# CTR_Precharge.net
KiCad netlist of a schematic drawn in Altium Designer
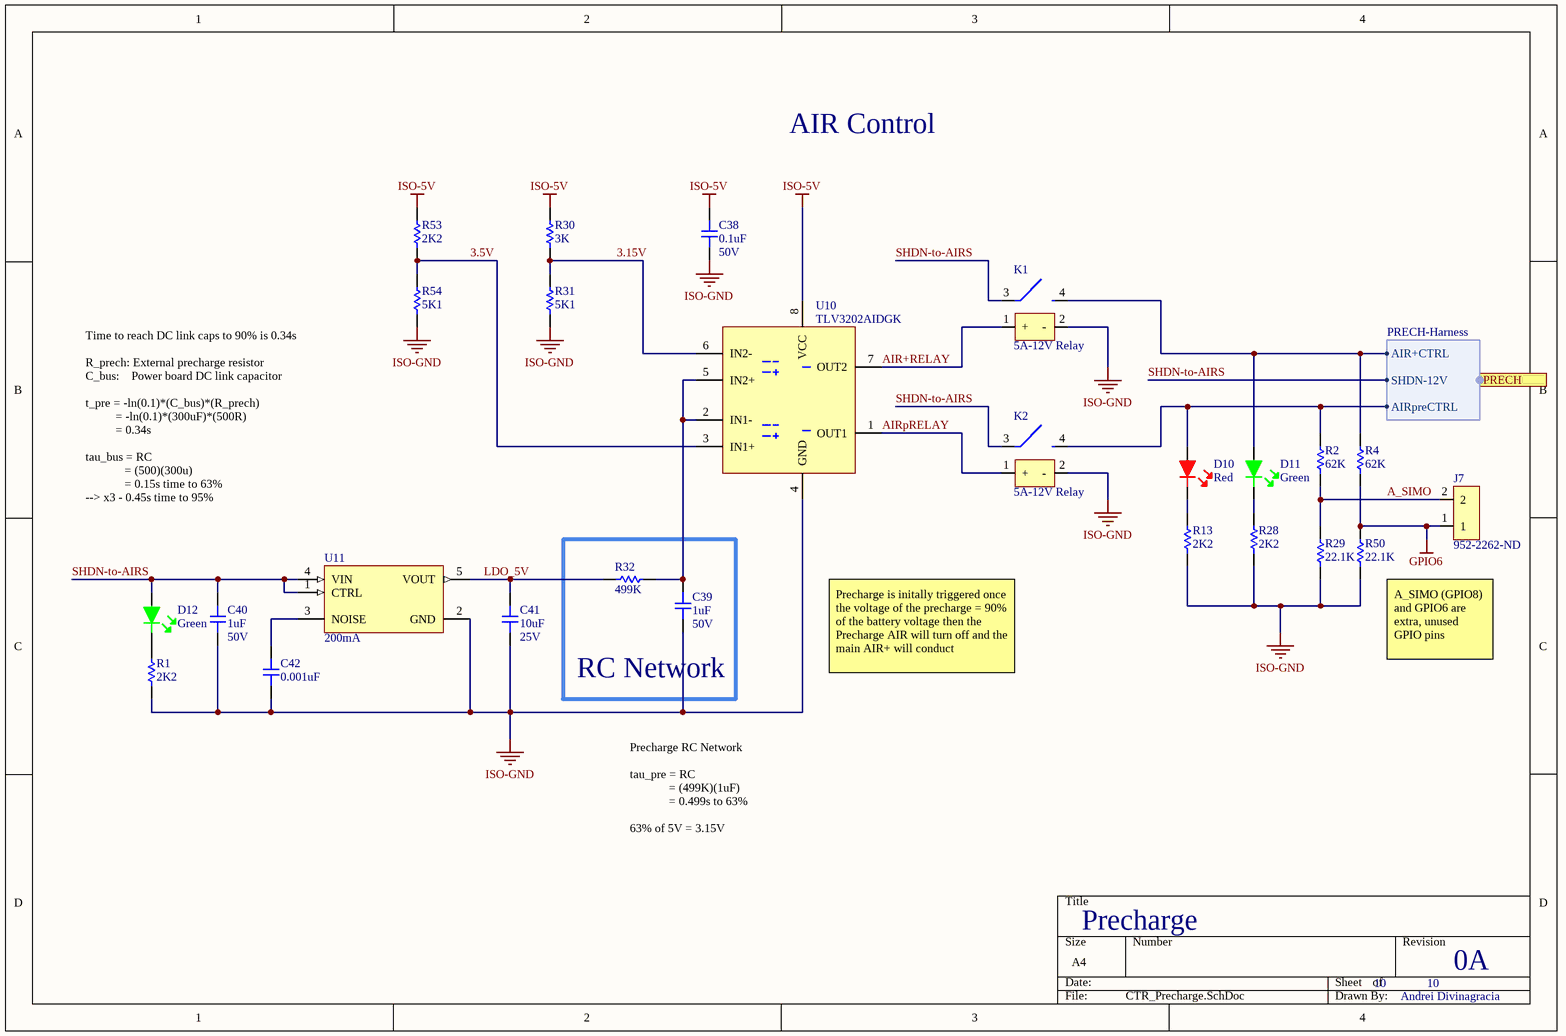
[diagram p0: CTR_Precharge.SchDoc]

(export (version "E")
  (design (tool "Eeschema 10.0.6"))
  (components
    (comp (ref "C38")
      (value "0.1uF")
      (footprint "CAP-0805")
      (description "CAP CER 0.1UF 50V Y5V 0805")
      (fields
        (field (name "MANUFACTURER") "KEMET")
        (field (name "MANUFACTURER PART NUMBER") "C0805C104Z5VACTU")
        (field (name "VOLTAGE RATING") "50V")
      )
      (libsource (lib "InverterSCHLib") (part "0805-0.1uF-50V"))
    )
    (comp (ref "C39")
      (value "1uF")
      (footprint "CAP-0805")
      (description "CAP CER 1UF 50V X5R 0805")
      (fields
        (field (name "MANUFACTURER") "KEMET")
        (field (name "MANUFACTURER PART NUMBER") "C0805C105K5PACTU")
        (field (name "VOLTAGE RATING") "50V")
      )
      (libsource (lib "InverterSCHLib") (part "0805-1uF-50V"))
    )
    (comp (ref "C40")
      (value "1uF")
      (footprint "CAP-0805")
      (description "CAP CER 1UF 50V X5R 0805")
      (fields
        (field (name "MANUFACTURER") "KEMET")
        (field (name "MANUFACTURER PART NUMBER") "C0805C105K5PACTU")
        (field (name "VOLTAGE RATING") "50V")
      )
      (libsource (lib "InverterSCHLib") (part "0805-1uF-50V"))
    )
    (comp (ref "C41")
      (value "10uF")
      (footprint "CAP-1206")
      (description "CAP CER 10UF 25V X7R 1206")
      (fields
        (field (name "MANUFACTURER") "Samsung")
        (field (name "MANUFACTURER PART NUMBER") "CL31B106KAHZW6E")
        (field (name "VOLTAGE RATING") "25V")
      )
      (libsource (lib "InverterSCHLib") (part "1206-10uF-25V"))
    )
    (comp (ref "C42")
      (value "0.001uF")
      (footprint "CAP-0603")
      (description "CAP CER 10000PF 50V X7R 0603")
      (fields
        (field (name "MANUFACTURER") "Kyocera AVX")
        (field (name "MANUFACTURER PART NUMBER") "06035C103KAT4A")
      )
      (libsource (lib "InverterSCHLib") (part "0603-10nF"))
    )
    (comp (ref "D10")
      (value "Red")
      (footprint "LED-0603")
      (description "LED RED CLEAR 0603 SMD")
      (fields
        (field (name "MANUFACTURER") "Wurth Electronics")
        (field (name "MANUFACTURER PART NUMBER") "150060RS75000")
      )
      (libsource (lib "InverterSCHLib") (part "LED-Red"))
    )
    (comp (ref "D11")
      (value "Green")
      (footprint "LED-0603")
      (description "LED GREEN CLEAR 0603 SMD")
      (fields
        (field (name "MANUFACTURER") "Wurth Electronics")
        (field (name "MANUFACTURER PART NUMBER") "150060VS75000")
      )
      (libsource (lib "InverterSCHLib") (part "LED-Green"))
    )
    (comp (ref "D12")
      (value "Green")
      (footprint "LED-0603")
      (description "LED GREEN CLEAR 0603 SMD")
      (fields
        (field (name "MANUFACTURER") "Wurth Electronics")
        (field (name "MANUFACTURER PART NUMBER") "150060VS75000")
      )
      (libsource (lib "InverterSCHLib") (part "LED-Green"))
    )
    (comp (ref "J7")
      (value "952-2262-ND")
      (footprint "2PIN_HEADER")
      (description "CONN HEADER VERT 2POS 2.54MM")
      (fields (field (name "MANUFACTURER") "Harwin") (field (name "MANUFACTURER PART NUMBER") "M20-9990246"))
      (libsource (lib "InverterSCHLib") (part "M20-9990246"))
    )
    (comp (ref "K1")
      (value "5A-12V Relay")
      (footprint "Relay")
      (description "General Purpose Relay SPST-NO (1 Form A) 12VDC Coil Through Hole")
      (fields
        (field (name "MANUFACTURER") "TE Connectivity")
        (field (name "MANUFACTURER PART NUMBER") "OJE-SH-112DM,000")
      )
      (libsource (lib "InverterSCHLib") (part "OJE-SH-112DM,000"))
    )
    (comp (ref "K2")
      (value "5A-12V Relay")
      (footprint "Relay")
      (description "General Purpose Relay SPST-NO (1 Form A) 12VDC Coil Through Hole")
      (fields
        (field (name "MANUFACTURER") "TE Connectivity")
        (field (name "MANUFACTURER PART NUMBER") "OJE-SH-112DM,000")
      )
      (libsource (lib "InverterSCHLib") (part "OJE-SH-112DM,000"))
    )
    (comp (ref "R1")
      (value "2K2")
      (footprint "RES-0603")
      (description "RES SMD 2.2K OHM 5% 1/10W 0603")
      (fields
        (field (name "MANUFACTURER") "Yageo")
        (field (name "MANUFACTURER PART NUMBER") "AC0603JR-072K2L")
      )
      (libsource (lib "InverterSCHLib") (part "0603-2K2"))
    )
    (comp (ref "R2")
      (value "62K")
      (footprint "RES-0603")
      (description "RES SMD 62K OHM 1% 1/4W 0603")
      (fields
        (field (name "MANUFACTURER") "Panasonic")
        (field (name "MANUFACTURER PART NUMBER") "ERJ-PA3F6202V")
      )
      (libsource (lib "InverterSCHLib") (part "0603-62K"))
    )
    (comp (ref "R4")
      (value "62K")
      (footprint "RES-0603")
      (description "RES SMD 62K OHM 1% 1/4W 0603")
      (fields
        (field (name "MANUFACTURER") "Panasonic")
        (field (name "MANUFACTURER PART NUMBER") "ERJ-PA3F6202V")
      )
      (libsource (lib "InverterSCHLib") (part "0603-62K"))
    )
    (comp (ref "R13")
      (value "2K2")
      (footprint "RES-0603")
      (description "RES SMD 2.2K OHM 5% 1/10W 0603")
      (fields
        (field (name "MANUFACTURER") "Yageo")
        (field (name "MANUFACTURER PART NUMBER") "AC0603JR-072K2L")
      )
      (libsource (lib "InverterSCHLib") (part "0603-2K2"))
    )
    (comp (ref "R28")
      (value "2K2")
      (footprint "RES-0603")
      (description "RES SMD 2.2K OHM 5% 1/10W 0603")
      (fields
        (field (name "MANUFACTURER") "Yageo")
        (field (name "MANUFACTURER PART NUMBER") "AC0603JR-072K2L")
      )
      (libsource (lib "InverterSCHLib") (part "0603-2K2"))
    )
    (comp (ref "R29")
      (value "22.1K")
      (footprint "RES-0603")
      (description "RES SMD 22.1K OHM 1% 1/10W 0603")
      (fields
        (field (name "MANUFACTURER") "Vishay")
        (field (name "MANUFACTURER PART NUMBER") "CRCW060322K1FKEA")
      )
      (libsource (lib "InverterSCHLib") (part "0603-22.1KR"))
    )
    (comp (ref "R30")
      (value "3K")
      (footprint "RES-0603")
      (description "RES SMD 3K OHM 5% 1/10W 0603")
      (fields
        (field (name "MANUFACTURER") "Yageo")
        (field (name "MANUFACTURER PART NUMBER") "RC0603JR-073KL")
      )
      (libsource (lib "InverterSCHLib") (part "0603-3KR"))
    )
    (comp (ref "R31")
      (value "5K1")
      (footprint "RES-0603")
      (description "RES SMD 5.1K OHM 1% 1/10W 0603")
      (fields
        (field (name "MANUFACTURER") "TE Connectivity")
        (field (name "MANUFACTURER PART NUMBER") "1623257-1")
      )
      (libsource (lib "InverterSCHLib") (part "0603-5.1KR"))
    )
    (comp (ref "R32")
      (value "499K")
      (footprint "RES-0603")
      (description "RES 499K OHM 1% 1/10W 0603")
      (fields
        (field (name "MANUFACTURER") "Vishay")
        (field (name "MANUFACTURER PART NUMBER") "CRCW0603499KFKEAC")
      )
      (libsource (lib "InverterSCHLib") (part "0603-499KR"))
    )
    (comp (ref "R50")
      (value "22.1K")
      (footprint "RES-0603")
      (description "RES SMD 22.1K OHM 1% 1/10W 0603")
      (fields
        (field (name "MANUFACTURER") "Vishay")
        (field (name "MANUFACTURER PART NUMBER") "CRCW060322K1FKEA")
      )
      (libsource (lib "InverterSCHLib") (part "0603-22.1KR"))
    )
    (comp (ref "R53")
      (value "2K2")
      (footprint "RES-0603")
      (description "RES SMD 2.2K OHM 5% 1/10W 0603")
      (fields
        (field (name "MANUFACTURER") "Yageo")
        (field (name "MANUFACTURER PART NUMBER") "AC0603JR-072K2L")
      )
      (libsource (lib "InverterSCHLib") (part "0603-2K2"))
    )
    (comp (ref "R54")
      (value "5K1")
      (footprint "RES-0603")
      (description "RES SMD 5.1K OHM 1% 1/10W 0603")
      (fields
        (field (name "MANUFACTURER") "TE Connectivity")
        (field (name "MANUFACTURER PART NUMBER") "1623257-1")
      )
      (libsource (lib "InverterSCHLib") (part "0603-5.1KR"))
    )
    (comp (ref "U10")
      (value "TLV3202AIDGK")
      (footprint "8VSSOP")
      (description "IC COMPAR PWR RRI DL PP 8VSSOP")
      (fields (field (name "MANUFACTURER") "Texas Instruments"))
      (libsource (lib "InverterSCHLib") (part "Compare-TLV3202AIDGK"))
    )
    (comp (ref "U11")
      (value "200mA")
      (footprint "SOT-753-ldo")
      (description "IC REG LINEAR 5V 200MA SMV")
      (fields
        (field (name "MANUFACTURER") "Toshiba")
        (field (name "MANUFACTURER PART NUMBER") "TAR5S50TE85LF")
      )
      (libsource (lib "InverterSCHLib") (part "TAR5S50TE85LF"))
    )
  )
  (nets
    (net (code "2") (name "/3.5V") (class "Default")
      (node (ref "R53") (pin "1") (pinfunction "1_1") (pintype "passive"))
      (node (ref "R54") (pin "2") (pinfunction "2_2") (pintype "passive"))
      (node (ref "U10") (pin "3") (pinfunction "IN1+_3") (pintype "passive"))
    )
    (net (code "3") (name "/3.15V") (class "Default")
      (node (ref "R30") (pin "1") (pinfunction "1_1") (pintype "passive"))
      (node (ref "R31") (pin "2") (pinfunction "2_2") (pintype "passive"))
      (node (ref "U10") (pin "6") (pinfunction "IN2-_6") (pintype "passive"))
    )
    (net (code "4") (name "/AIR+RELAY") (class "Default")
      (node (ref "K1") (pin "1") (pinfunction "+_1") (pintype "passive"))
      (node (ref "U10") (pin "7") (pinfunction "OUT2_7") (pintype "passive"))
    )
    (net (code "5") (name "/AIRpRELAY") (class "Default")
      (node (ref "K2") (pin "1") (pinfunction "+_1") (pintype "passive"))
      (node (ref "U10") (pin "1") (pinfunction "OUT1_1") (pintype "passive"))
    )
    (net (code "6") (name "/A_SIMO") (class "Default")
      (node (ref "J7") (pin "2") (pinfunction "2_2") (pintype "passive"))
      (node (ref "R2") (pin "1") (pinfunction "1_1") (pintype "passive"))
      (node (ref "R29") (pin "2") (pinfunction "2_2") (pintype "passive"))
    )
    (net (code "7") (name "/LDO_5V") (class "Default")
      (node (ref "C41") (pin "2") (pinfunction "2_2") (pintype "passive"))
      (node (ref "R32") (pin "1") (pinfunction "1_1") (pintype "passive"))
      (node (ref "U11") (pin "5") (pinfunction "VOUT_5") (pintype "output"))
    )
    (net (code "8") (name "/SHDN-to-AIRS") (class "Default")
      (node (ref "C40") (pin "2") (pinfunction "2_2") (pintype "passive"))
      (node (ref "D12") (pin "1") (pinfunction "1_1") (pintype "passive"))
      (node (ref "K1") (pin "3") (pinfunction "3_3") (pintype "passive"))
      (node (ref "K2") (pin "3") (pinfunction "3_3") (pintype "passive"))
      (node (ref "U11") (pin "1") (pinfunction "CTRL_1") (pintype "input"))
      (node (ref "U11") (pin "4") (pinfunction "VIN_4") (pintype "input"))
    )
    (net (code "10") (name "GPIO6") (class "Default")
      (node (ref "J7") (pin "1") (pinfunction "1_1") (pintype "passive"))
      (node (ref "R4") (pin "1") (pinfunction "1_1") (pintype "passive"))
      (node (ref "R50") (pin "2") (pinfunction "2_2") (pintype "passive"))
    )
    (net (code "11") (name "ISO-5V") (class "Default")
      (node (ref "C38") (pin "2") (pinfunction "2_2") (pintype "passive"))
      (node (ref "R30") (pin "2") (pinfunction "2_2") (pintype "passive"))
      (node (ref "R53") (pin "2") (pinfunction "2_2") (pintype "passive"))
      (node (ref "U10") (pin "8") (pinfunction "VCC_8") (pintype "passive"))
    )
    (net (code "12") (name "ISO-GND") (class "Default")
      (node (ref "C38") (pin "1") (pinfunction "1_1") (pintype "passive"))
      (node (ref "C39") (pin "1") (pinfunction "1_1") (pintype "passive"))
      (node (ref "C40") (pin "1") (pinfunction "1_1") (pintype "passive"))
      (node (ref "C41") (pin "1") (pinfunction "1_1") (pintype "passive"))
      (node (ref "C42") (pin "2") (pinfunction "2_2") (pintype "passive"))
      (node (ref "K1") (pin "2") (pinfunction "-_2") (pintype "passive"))
      (node (ref "K2") (pin "2") (pinfunction "-_2") (pintype "passive"))
      (node (ref "R1") (pin "1") (pinfunction "1_1") (pintype "passive"))
      (node (ref "R13") (pin "1") (pinfunction "1_1") (pintype "passive"))
      (node (ref "R28") (pin "1") (pinfunction "1_1") (pintype "passive"))
      (node (ref "R29") (pin "1") (pinfunction "1_1") (pintype "passive"))
      (node (ref "R31") (pin "1") (pinfunction "1_1") (pintype "passive"))
      (node (ref "R50") (pin "1") (pinfunction "1_1") (pintype "passive"))
      (node (ref "R54") (pin "1") (pinfunction "1_1") (pintype "passive"))
      (node (ref "U10") (pin "4") (pinfunction "GND_4") (pintype "passive"))
      (node (ref "U11") (pin "2") (pinfunction "GND_2") (pintype "passive"))
    )
    (net (code "13") (name "Net-(D10-Pad1)") (class "Default")
      (node (ref "D10") (pin "1") (pinfunction "1_1") (pintype "passive"))
      (node (ref "K2") (pin "4") (pinfunction "4_4") (pintype "passive"))
      (node (ref "R2") (pin "2") (pinfunction "2_2") (pintype "passive"))
    )
    (net (code "14") (name "Net-(D10-Pad2)") (class "Default")
      (node (ref "D10") (pin "2") (pinfunction "2_2") (pintype "passive"))
      (node (ref "R13") (pin "2") (pinfunction "2_2") (pintype "passive"))
    )
    (net (code "15") (name "Net-(D11-Pad1)") (class "Default")
      (node (ref "D11") (pin "1") (pinfunction "1_1") (pintype "passive"))
      (node (ref "K1") (pin "4") (pinfunction "4_4") (pintype "passive"))
      (node (ref "R4") (pin "2") (pinfunction "2_2") (pintype "passive"))
    )
    (net (code "16") (name "Net-(D11-Pad2)") (class "Default")
      (node (ref "D11") (pin "2") (pinfunction "2_2") (pintype "passive"))
      (node (ref "R28") (pin "2") (pinfunction "2_2") (pintype "passive"))
    )
    (net (code "17") (name "Net-(D12-Pad2)") (class "Default")
      (node (ref "D12") (pin "2") (pinfunction "2_2") (pintype "passive"))
      (node (ref "R1") (pin "2") (pinfunction "2_2") (pintype "passive"))
    )
    (net (code "18") (name "Net-(U10-IN1-)") (class "Default")
      (node (ref "C39") (pin "2") (pinfunction "2_2") (pintype "passive"))
      (node (ref "R32") (pin "2") (pinfunction "2_2") (pintype "passive"))
      (node (ref "U10") (pin "2") (pinfunction "IN1-_2") (pintype "passive"))
      (node (ref "U10") (pin "5") (pinfunction "IN2+_5") (pintype "passive"))
    )
    (net (code "19") (name "Net-(U11-NOISE)") (class "Default")
      (node (ref "C42") (pin "1") (pinfunction "1_1") (pintype "passive"))
      (node (ref "U11") (pin "3") (pinfunction "NOISE_3") (pintype "passive"))
    )
  )
)
